# H_Bridge.net
KiCad netlist of a schematic drawn in Altium Designer
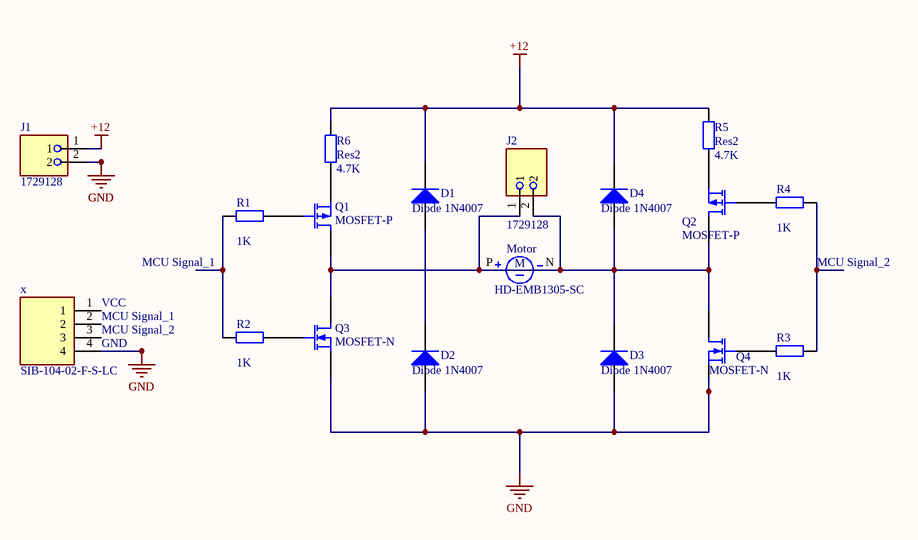
[diagram p0: H_Bridge.SchDoc]

(export (version "E")
  (design (tool "Eeschema 10.0.6"))
  (components
    (comp (ref "D1")
      (value "Diode 1N4007")
      (footprint "DO-41")
      (description "1 Amp General Purpose Rectifier")
      (fields (field (name "PUBLISHER") "Altium Limited"))
      (libsource (lib "Miscellaneous Devices") (part "Diode 1N4007"))
    )
    (comp (ref "D2")
      (value "Diode 1N4007")
      (footprint "DO-41")
      (description "1 Amp General Purpose Rectifier")
      (fields (field (name "PUBLISHER") "Altium Limited"))
      (libsource (lib "Miscellaneous Devices") (part "Diode 1N4007"))
    )
    (comp (ref "D3")
      (value "Diode 1N4007")
      (footprint "DO-41")
      (description "1 Amp General Purpose Rectifier")
      (fields (field (name "PUBLISHER") "Altium Limited"))
      (libsource (lib "Miscellaneous Devices") (part "Diode 1N4007"))
    )
    (comp (ref "D4")
      (value "Diode 1N4007")
      (footprint "DO-41")
      (description "1 Amp General Purpose Rectifier")
      (fields (field (name "PUBLISHER") "Altium Limited"))
      (libsource (lib "Miscellaneous Devices") (part "Diode 1N4007"))
    )
    (comp (ref "J1")
      (value "1729128")
      (footprint "PHOENIX_1729128")
      (fields (field (name "MF") "Phoenix Contact"))
      (libsource (lib "") (part "1729128_1"))
    )
    (comp (ref "J2")
      (value "1729128")
      (footprint "PHOENIX_1729128")
      (fields (field (name "MF") "Phoenix Contact"))
      (libsource (lib "1729128") (part "1729128"))
    )
    (comp (ref "Motor")
      (value "HD-EMB1305-SC")
      (footprint "PUI_HD-EMB1305-SC")
      (description "HD MOTOR 3VDC 93OHM 13000RPM")
      (fields (field (name "MF") "PUI Audio"))
      (libsource (lib "HD-EMB1305-SC") (part "HD-EMB1305-SC"))
    )
    (comp (ref "Q1")
      (value "MOSFET-P")
      (footprint "E3")
      (description "P-Channel MOSFET")
      (fields (field (name "PUBLISHER") "Altium Limited"))
      (libsource (lib "Miscellaneous Devices") (part "MOSFET-P"))
    )
    (comp (ref "Q2")
      (value "MOSFET-P")
      (footprint "E3")
      (description "P-Channel MOSFET")
      (fields (field (name "PUBLISHER") "Altium Limited"))
      (libsource (lib "Miscellaneous Devices") (part "MOSFET-P"))
    )
    (comp (ref "Q3")
      (value "MOSFET-N")
      (footprint "E3")
      (description "N-Channel MOSFET")
      (fields (field (name "PUBLISHER") "Altium Limited"))
      (libsource (lib "Miscellaneous Devices") (part "MOSFET-N"))
    )
    (comp (ref "Q4")
      (value "MOSFET-N")
      (footprint "E3")
      (description "N-Channel MOSFET")
      (fields (field (name "PUBLISHER") "Altium Limited"))
      (libsource (lib "Miscellaneous Devices") (part "MOSFET-N"))
    )
    (comp (ref "R1")
      (value "1K")
      (footprint "AXIAL-0.4")
      (description "Resistor")
      (fields (field (name "Comment") "Res2") (field (name "PUBLISHER") "Altium Limited"))
      (libsource (lib "Miscellaneous Devices") (part "Res2"))
    )
    (comp (ref "R2")
      (value "1K")
      (footprint "AXIAL-0.4")
      (description "Resistor")
      (fields (field (name "Comment") "Res2") (field (name "PUBLISHER") "Altium Limited"))
      (libsource (lib "Miscellaneous Devices") (part "Res2"))
    )
    (comp (ref "R3")
      (value "1K")
      (footprint "AXIAL-0.4")
      (description "Resistor")
      (fields (field (name "Comment") "Res2") (field (name "PUBLISHER") "Altium Limited"))
      (libsource (lib "Miscellaneous Devices") (part "Res2"))
    )
    (comp (ref "R4")
      (value "1K")
      (footprint "AXIAL-0.4")
      (description "Resistor")
      (fields (field (name "Comment") "Res2") (field (name "PUBLISHER") "Altium Limited"))
      (libsource (lib "Miscellaneous Devices") (part "Res2"))
    )
    (comp (ref "R5")
      (value "Res2")
      (footprint "AXIAL-0.4")
      (description "Resistor")
      (fields (field (name "ALTIUM_VALUE") "4.7K") (field (name "PUBLISHER") "Altium Limited"))
      (libsource (lib "") (part "Res2_1"))
    )
    (comp (ref "R6")
      (value "Res2")
      (footprint "AXIAL-0.4")
      (description "Resistor")
      (fields (field (name "ALTIUM_VALUE") "4.7K") (field (name "PUBLISHER") "Altium Limited"))
      (libsource (lib "") (part "Res2_1"))
    )
    (comp (ref "x")
      (value "SIB-104-02-F-S-LC")
      (footprint "SAMTEC_SIB-104-02-F-S-LC")
      (description "SIB Series .100\" One-Piece Interface")
      (libsource (lib "SIB-104-02-F-S-LC") (part "SIB-104-02-F-S-LC"))
    )
  )
  (nets
    (net (code "1") (name "+12") (class "Default")
      (node (ref "D1") (pin "2") (pinfunction "K_2") (pintype "passive"))
      (node (ref "D4") (pin "2") (pinfunction "K_2") (pintype "passive"))
      (node (ref "J1") (pin "1") (pinfunction "1_1") (pintype "passive"))
      (node (ref "R5") (pin "2") (pinfunction "2_2") (pintype "passive"))
      (node (ref "R6") (pin "2") (pinfunction "2_2") (pintype "passive"))
    )
    (net (code "2") (name "GND") (class "Default")
      (node (ref "D2") (pin "1") (pinfunction "A_1") (pintype "passive"))
      (node (ref "D3") (pin "1") (pinfunction "A_1") (pintype "passive"))
      (node (ref "J1") (pin "2") (pinfunction "2_2") (pintype "passive"))
      (node (ref "Q3") (pin "3") (pinfunction "S_3") (pintype "passive"))
      (node (ref "Q4") (pin "3") (pinfunction "S_3") (pintype "passive"))
      (node (ref "x") (pin "4") (pinfunction "4_4") (pintype "passive"))
    )
    (net (code "3") (name "Net-(D1-A)") (class "Default")
      (node (ref "D1") (pin "1") (pinfunction "A_1") (pintype "passive"))
      (node (ref "D2") (pin "2") (pinfunction "K_2") (pintype "passive"))
    )
    (net (code "4") (name "Net-(D3-K)") (class "Default")
      (node (ref "D3") (pin "2") (pinfunction "K_2") (pintype "passive"))
      (node (ref "D4") (pin "1") (pinfunction "A_1") (pintype "passive"))
      (node (ref "J2") (pin "1") (pinfunction "1_1") (pintype "passive"))
      (node (ref "J2") (pin "2") (pinfunction "2_2") (pintype "passive"))
      (node (ref "Motor") (pin "N") (pinfunction "NEG_N") (pintype "passive"))
      (node (ref "Motor") (pin "P") (pinfunction "POS_P") (pintype "passive"))
      (node (ref "Q1") (pin "1") (pinfunction "D_1") (pintype "passive"))
      (node (ref "Q2") (pin "1") (pinfunction "D_1") (pintype "passive"))
      (node (ref "Q3") (pin "1") (pinfunction "D_1") (pintype "passive"))
      (node (ref "Q4") (pin "1") (pinfunction "D_1") (pintype "passive"))
    )
    (net (code "5") (name "Net-(Q1-G)") (class "Default")
      (node (ref "Q1") (pin "2") (pinfunction "G_2") (pintype "passive"))
      (node (ref "R1") (pin "2") (pinfunction "2_2") (pintype "passive"))
    )
    (net (code "6") (name "Net-(Q1-S)") (class "Default")
      (node (ref "Q1") (pin "3") (pinfunction "S_3") (pintype "passive"))
      (node (ref "R6") (pin "1") (pinfunction "1_1") (pintype "passive"))
    )
    (net (code "7") (name "Net-(Q2-G)") (class "Default")
      (node (ref "Q2") (pin "2") (pinfunction "G_2") (pintype "passive"))
      (node (ref "R4") (pin "1") (pinfunction "1_1") (pintype "passive"))
    )
    (net (code "8") (name "Net-(Q2-S)") (class "Default")
      (node (ref "Q2") (pin "3") (pinfunction "S_3") (pintype "passive"))
      (node (ref "R5") (pin "1") (pinfunction "1_1") (pintype "passive"))
    )
    (net (code "9") (name "Net-(Q3-G)") (class "Default")
      (node (ref "Q3") (pin "2") (pinfunction "G_2") (pintype "passive"))
      (node (ref "R2") (pin "2") (pinfunction "2_2") (pintype "passive"))
    )
    (net (code "10") (name "Net-(Q4-G)") (class "Default")
      (node (ref "Q4") (pin "2") (pinfunction "G_2") (pintype "passive"))
      (node (ref "R3") (pin "1") (pinfunction "1_1") (pintype "passive"))
    )
    (net (code "11") (name "Net-(R1-Pad1)") (class "Default")
      (node (ref "R1") (pin "1") (pinfunction "1_1") (pintype "passive"))
      (node (ref "R2") (pin "1") (pinfunction "1_1") (pintype "passive"))
    )
    (net (code "12") (name "Net-(R3-Pad2)") (class "Default")
      (node (ref "R3") (pin "2") (pinfunction "2_2") (pintype "passive"))
      (node (ref "R4") (pin "2") (pinfunction "2_2") (pintype "passive"))
    )
    (net (code "13") (name "unconnected-(x-Pad1)") (class "Default")
      (node (ref "x") (pin "1") (pinfunction "1_1") (pintype "passive"))
    )
    (net (code "14") (name "unconnected-(x-Pad2)") (class "Default")
      (node (ref "x") (pin "2") (pinfunction "2_2") (pintype "passive"))
    )
    (net (code "15") (name "unconnected-(x-Pad3)") (class "Default")
      (node (ref "x") (pin "3") (pinfunction "3_3") (pintype "passive"))
    )
  )
)
